# AstableMultivibrator-NPN-CapPol-LED.net
KiCad netlist of a schematic drawn in EAGLE
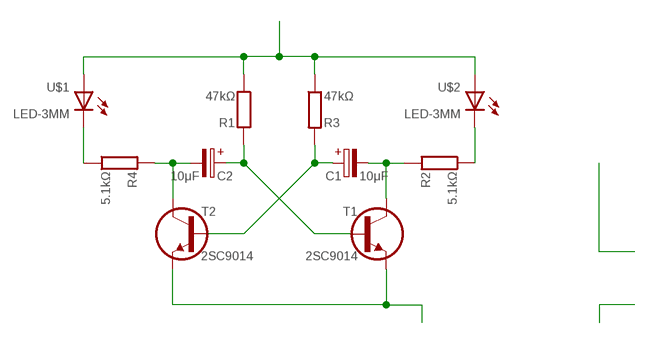
[diagram p0: schematic, sheet 1]

(export (version "E")
  (design (tool "Eeschema 10.0.6"))
  (components
    (comp (ref "C1")
      (value "10μF")
      (footprint "eagle-import:E2,5-4")
      (libsource (lib "eagle-import") (part "CPOL-HE2,5-4"))
    )
    (comp (ref "C2")
      (value "10μF")
      (footprint "eagle-import:E2,5-4")
      (libsource (lib "eagle-import") (part "CPOL-HE2,5-4"))
    )
    (comp (ref "R1")
      (value "47kΩ")
      (footprint "eagle-import:0202_7-V")
      (libsource (lib "eagle-import") (part "R0202/7-V"))
    )
    (comp (ref "R2")
      (value "5.1kΩ")
      (footprint "eagle-import:0202_7-V")
      (libsource (lib "eagle-import") (part "R0202/7-V"))
    )
    (comp (ref "R3")
      (value "47kΩ")
      (footprint "eagle-import:0202_7-V")
      (libsource (lib "eagle-import") (part "R0202/7-V"))
    )
    (comp (ref "R4")
      (value "5.1kΩ")
      (footprint "eagle-import:0202_7-V")
      (libsource (lib "eagle-import") (part "R0202/7-V"))
    )
    (comp (ref "T1")
      (value "2SC9014")
      (footprint "eagle-import:TO92-EBC")
      (libsource (lib "eagle-import") (part "2SC9014"))
    )
    (comp (ref "T2")
      (value "2SC9014")
      (footprint "eagle-import:TO92-EBC")
      (libsource (lib "eagle-import") (part "2SC9014"))
    )
    (comp (ref "U$1")
      (value "LED-3MM")
      (footprint "eagle-import:LED_3MM")
      (libsource (lib "eagle-import") (part "LED-3MM"))
    )
    (comp (ref "U$2")
      (value "LED-3MM")
      (footprint "eagle-import:LED_3MM")
      (libsource (lib "eagle-import") (part "LED-3MM"))
    )
  )
  (nets
    (net (code "1") (name "Net-(R1-1)") (class "Default")
      (node (ref "C2") (pin "+") (pinfunction "+_+") (pintype "passive"))
      (node (ref "R1") (pin "2") (pinfunction "1_2") (pintype "passive"))
      (node (ref "T1") (pin "B") (pinfunction "B_B") (pintype "passive"))
    )
    (net (code "2") (name "Net-(R1-2)") (class "Default")
      (node (ref "R1") (pin "1") (pinfunction "2_1") (pintype "passive"))
      (node (ref "R3") (pin "1") (pinfunction "2_1") (pintype "passive"))
      (node (ref "U$1") (pin "A") (pinfunction "A_A") (pintype "passive"))
      (node (ref "U$2") (pin "A") (pinfunction "A_A") (pintype "passive"))
    )
    (net (code "3") (name "Net-(R2-1)") (class "Default")
      (node (ref "C1") (pin "-") (pinfunction "-_-") (pintype "passive"))
      (node (ref "R2") (pin "2") (pinfunction "1_2") (pintype "passive"))
      (node (ref "T1") (pin "C") (pinfunction "C_C") (pintype "passive"))
    )
    (net (code "4") (name "Net-(R2-2)") (class "Default")
      (node (ref "R2") (pin "1") (pinfunction "2_1") (pintype "passive"))
      (node (ref "U$2") (pin "K") (pinfunction "C_K") (pintype "passive"))
    )
    (net (code "5") (name "Net-(R3-1)") (class "Default")
      (node (ref "C1") (pin "+") (pinfunction "+_+") (pintype "passive"))
      (node (ref "R3") (pin "2") (pinfunction "1_2") (pintype "passive"))
      (node (ref "T2") (pin "B") (pinfunction "B_B") (pintype "passive"))
    )
    (net (code "6") (name "Net-(R4-1)") (class "Default")
      (node (ref "C2") (pin "-") (pinfunction "-_-") (pintype "passive"))
      (node (ref "R4") (pin "2") (pinfunction "1_2") (pintype "passive"))
      (node (ref "T2") (pin "C") (pinfunction "C_C") (pintype "passive"))
    )
    (net (code "7") (name "Net-(R4-2)") (class "Default")
      (node (ref "R4") (pin "1") (pinfunction "2_1") (pintype "passive"))
      (node (ref "U$1") (pin "K") (pinfunction "C_K") (pintype "passive"))
    )
    (net (code "8") (name "Net-(T1-PadE)") (class "Default")
      (node (ref "T1") (pin "E") (pinfunction "E_E") (pintype "passive"))
      (node (ref "T2") (pin "E") (pinfunction "E_E") (pintype "passive"))
    )
  )
)
